# ETH.net
KiCad netlist of a schematic drawn in Altium Designer
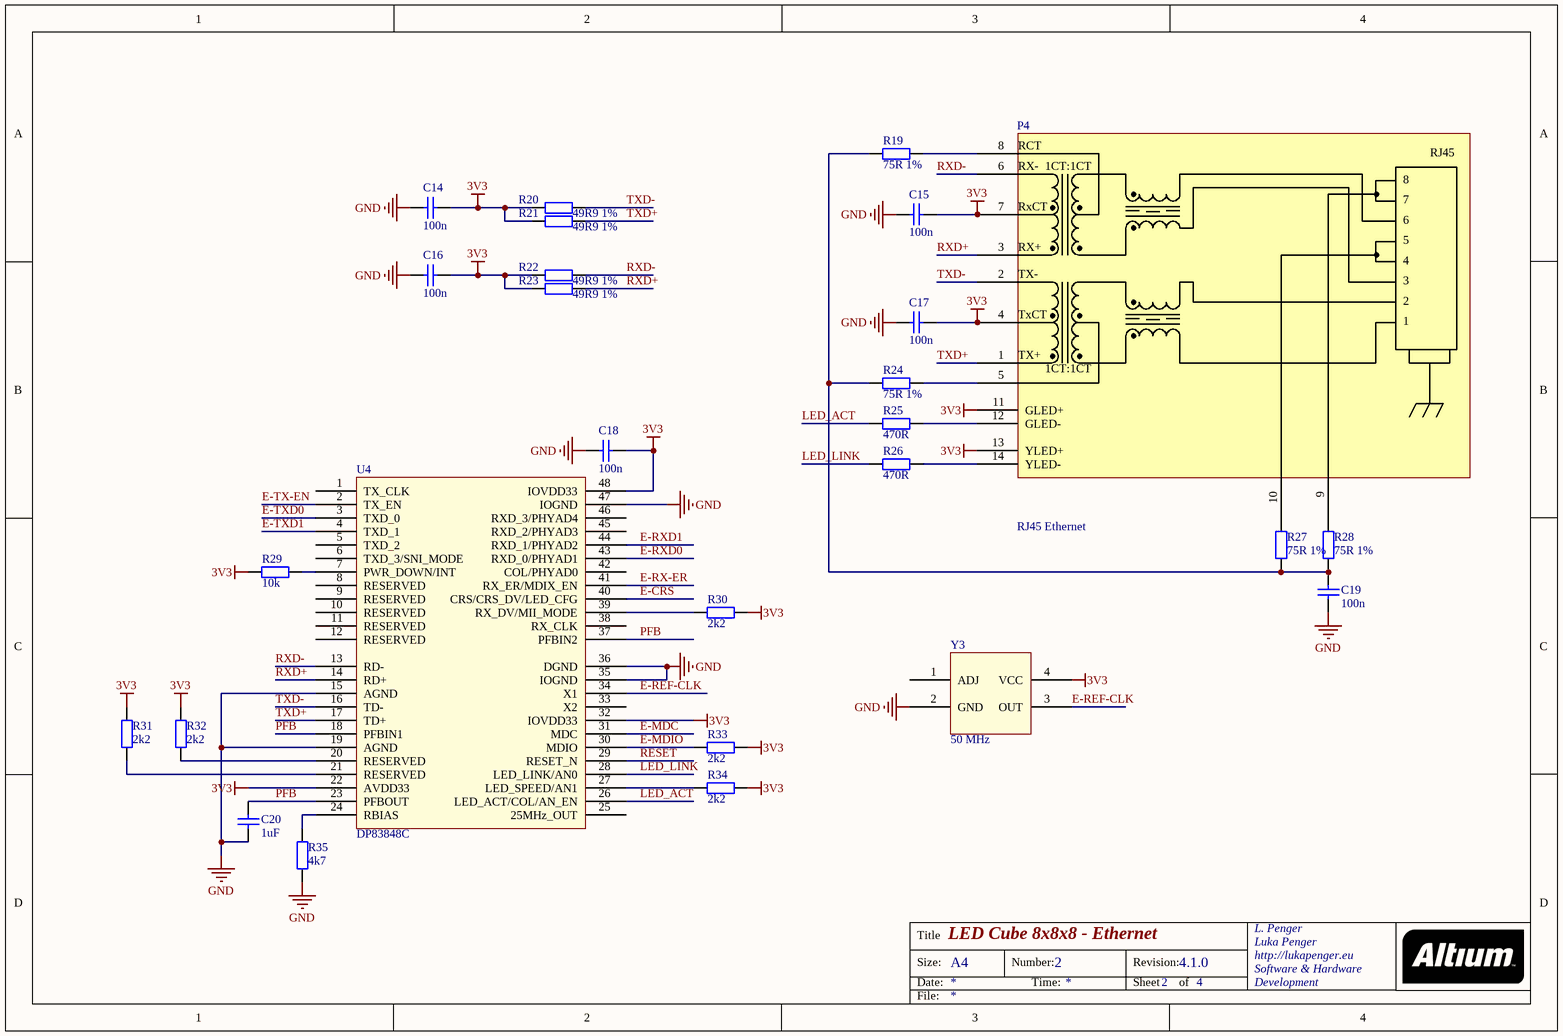
[diagram p0: ETH.SchDoc]

(export (version "E")
  (design (tool "Eeschema 10.0.6"))
  (components
    (comp (ref "C14")
      (value "100n")
      (footprint "1608[0603]")
      (description "Capacitor")
      (fields (field (name "PUBLISHER") "Altium Limited"))
      (libsource (lib "Miscellaneous Devices") (part "Cap"))
    )
    (comp (ref "C15")
      (value "100n")
      (footprint "1608[0603]")
      (description "Capacitor")
      (fields (field (name "PUBLISHER") "Altium Limited"))
      (libsource (lib "Miscellaneous Devices") (part "Cap"))
    )
    (comp (ref "C16")
      (value "100n")
      (footprint "1608[0603]")
      (description "Capacitor")
      (fields (field (name "PUBLISHER") "Altium Limited"))
      (libsource (lib "Miscellaneous Devices") (part "Cap"))
    )
    (comp (ref "C17")
      (value "100n")
      (footprint "1608[0603]")
      (description "Capacitor")
      (fields (field (name "PUBLISHER") "Altium Limited"))
      (libsource (lib "Miscellaneous Devices") (part "Cap"))
    )
    (comp (ref "C18")
      (value "100n")
      (footprint "1608[0603]")
      (description "Capacitor")
      (fields (field (name "PUBLISHER") "Altium Limited"))
      (libsource (lib "Miscellaneous Devices") (part "Cap"))
    )
    (comp (ref "C19")
      (value "100n")
      (footprint "1608[0603]")
      (description "Capacitor")
      (fields (field (name "PUBLISHER") "Altium Limited"))
      (libsource (lib "Miscellaneous Devices") (part "Cap"))
    )
    (comp (ref "C20")
      (value "1uF")
      (footprint "6-0805_L")
      (description "Capacitor")
      (fields (field (name "PUBLISHER") "Altium Limited"))
      (libsource (lib "Miscellaneous Devices") (part "Cap"))
    )
    (comp (ref "P4")
      (value "RJ45 Ethernet")
      (footprint "RJ45 Ethernet connector")
      (description "Ethernet Connector")
      (libsource (lib "LP_Lib") (part "RJ45 Ethernet"))
    )
    (comp (ref "R19")
      (value "75R 1%")
      (footprint "1608[0603]")
      (description "Resistor")
      (fields (field (name "PUBLISHER") "Altium Limited"))
      (libsource (lib "") (part "Res2_1"))
    )
    (comp (ref "R20")
      (value "49R9 1%")
      (footprint "1608[0603]")
      (description "Resistor")
      (fields (field (name "PUBLISHER") "Altium Limited"))
      (libsource (lib "") (part "Res2_1"))
    )
    (comp (ref "R21")
      (value "49R9 1%")
      (footprint "1608[0603]")
      (description "Resistor")
      (fields (field (name "PUBLISHER") "Altium Limited"))
      (libsource (lib "") (part "Res2_1"))
    )
    (comp (ref "R22")
      (value "49R9 1%")
      (footprint "1608[0603]")
      (description "Resistor")
      (fields (field (name "PUBLISHER") "Altium Limited"))
      (libsource (lib "") (part "Res2_1"))
    )
    (comp (ref "R23")
      (value "49R9 1%")
      (footprint "1608[0603]")
      (description "Resistor")
      (fields (field (name "PUBLISHER") "Altium Limited"))
      (libsource (lib "") (part "Res2_1"))
    )
    (comp (ref "R24")
      (value "75R 1%")
      (footprint "1608[0603]")
      (description "Resistor")
      (fields (field (name "PUBLISHER") "Altium Limited"))
      (libsource (lib "") (part "Res2_1"))
    )
    (comp (ref "R25")
      (value "470R")
      (footprint "1608[0603]")
      (description "Resistor")
      (fields (field (name "PUBLISHER") "Altium Limited"))
      (libsource (lib "") (part "Res2_1"))
    )
    (comp (ref "R26")
      (value "470R")
      (footprint "1608[0603]")
      (description "Resistor")
      (fields (field (name "PUBLISHER") "Altium Limited"))
      (libsource (lib "") (part "Res2_1"))
    )
    (comp (ref "R27")
      (value "75R 1%")
      (footprint "1608[0603]")
      (description "Resistor")
      (fields (field (name "PUBLISHER") "Altium Limited"))
      (libsource (lib "Miscellaneous Devices") (part "Res2"))
    )
    (comp (ref "R28")
      (value "75R 1%")
      (footprint "1608[0603]")
      (description "Resistor")
      (fields (field (name "PUBLISHER") "Altium Limited"))
      (libsource (lib "Miscellaneous Devices") (part "Res2"))
    )
    (comp (ref "R29")
      (value "10k")
      (footprint "1608[0603]")
      (description "Resistor")
      (fields (field (name "PUBLISHER") "Altium Limited"))
      (libsource (lib "") (part "Res2_1"))
    )
    (comp (ref "R30")
      (value "2k2")
      (footprint "1608[0603]")
      (description "Resistor")
      (fields (field (name "PUBLISHER") "Altium Limited"))
      (libsource (lib "") (part "Res2_1"))
    )
    (comp (ref "R31")
      (value "2k2")
      (footprint "1608[0603]")
      (description "Resistor")
      (fields (field (name "PUBLISHER") "Altium Limited"))
      (libsource (lib "") (part "Res2_2"))
    )
    (comp (ref "R32")
      (value "2k2")
      (footprint "1608[0603]")
      (description "Resistor")
      (fields (field (name "PUBLISHER") "Altium Limited"))
      (libsource (lib "Miscellaneous Devices") (part "Res2"))
    )
    (comp (ref "R33")
      (value "2k2")
      (footprint "1608[0603]")
      (description "Resistor")
      (fields (field (name "PUBLISHER") "Altium Limited"))
      (libsource (lib "") (part "Res2_1"))
    )
    (comp (ref "R34")
      (value "2k2")
      (footprint "1608[0603]")
      (description "Resistor")
      (fields (field (name "PUBLISHER") "Altium Limited"))
      (libsource (lib "") (part "Res2_1"))
    )
    (comp (ref "R35")
      (value "4k7")
      (footprint "1608[0603]")
      (description "Resistor")
      (fields (field (name "PUBLISHER") "Altium Limited"))
      (libsource (lib "") (part "Res2_2"))
    )
    (comp (ref "U4")
      (value "DP83848C")
      (footprint "DP83848C")
      (description "Ethernet PHY")
      (libsource (lib "LP_Lib") (part "DP83848C"))
    )
    (comp (ref "Y3")
      (value "50 MHz")
      (footprint "XTAL ACT9200 5x7mm")
      (libsource (lib "LukaLIBRARY") (part "XTAL ACT9200"))
    )
  )
  (nets
    (net (code "1") (name "/E-CRS") (class "Default")
      (node (ref "U4") (pin "40") (pinfunction "CRS/CRS_DV/LED_CFG_40") (pintype "passive"))
    )
    (net (code "2") (name "/E-MDC") (class "Default")
      (node (ref "U4") (pin "31") (pinfunction "MDC_31") (pintype "passive"))
    )
    (net (code "3") (name "/E-MDIO") (class "Default")
      (node (ref "R33") (pin "2") (pinfunction "2_2") (pintype "passive"))
      (node (ref "U4") (pin "30") (pinfunction "MDIO_30") (pintype "passive"))
    )
    (net (code "4") (name "/E-REF-CLK") (class "Default")
      (node (ref "U4") (pin "34") (pinfunction "X1_34") (pintype "passive"))
      (node (ref "Y3") (pin "3") (pinfunction "OUT_3") (pintype "passive"))
    )
    (net (code "5") (name "/E-RX-ER") (class "Default")
      (node (ref "U4") (pin "41") (pinfunction "RX_ER/MDIX_EN_41") (pintype "passive"))
    )
    (net (code "6") (name "/E-RXD0") (class "Default")
      (node (ref "U4") (pin "43") (pinfunction "RXD_0/PHYAD1_43") (pintype "passive"))
    )
    (net (code "7") (name "/E-RXD1") (class "Default")
      (node (ref "U4") (pin "44") (pinfunction "RXD_1/PHYAD2_44") (pintype "passive"))
    )
    (net (code "8") (name "/E-TX-EN") (class "Default")
      (node (ref "U4") (pin "2") (pinfunction "TX_EN_2") (pintype "passive"))
    )
    (net (code "9") (name "/E-TXD0") (class "Default")
      (node (ref "U4") (pin "3") (pinfunction "TXD_0_3") (pintype "passive"))
    )
    (net (code "10") (name "/E-TXD1") (class "Default")
      (node (ref "U4") (pin "4") (pinfunction "TXD_1_4") (pintype "passive"))
    )
    (net (code "11") (name "/LED_ACT") (class "Default")
      (node (ref "R25") (pin "2") (pinfunction "2_2") (pintype "passive"))
      (node (ref "U4") (pin "26") (pinfunction "LED_ACT/COL/AN_EN_26") (pintype "passive"))
    )
    (net (code "12") (name "/LED_LINK") (class "Default")
      (node (ref "R26") (pin "2") (pinfunction "2_2") (pintype "passive"))
      (node (ref "U4") (pin "28") (pinfunction "LED_LINK/AN0_28") (pintype "passive"))
    )
    (net (code "13") (name "/PFB") (class "Default")
      (node (ref "C20") (pin "1") (pinfunction "1_1") (pintype "passive"))
      (node (ref "U4") (pin "18") (pinfunction "PFBIN1_18") (pintype "passive"))
      (node (ref "U4") (pin "23") (pinfunction "PFBOUT_23") (pintype "passive"))
      (node (ref "U4") (pin "37") (pinfunction "PFBIN2_37") (pintype "passive"))
    )
    (net (code "14") (name "/RESET") (class "Default")
      (node (ref "U4") (pin "29") (pinfunction "RESET_N_29") (pintype "passive"))
    )
    (net (code "15") (name "/RXD+") (class "Default")
      (node (ref "P4") (pin "3") (pintype "passive"))
      (node (ref "R23") (pin "1") (pinfunction "1_1") (pintype "passive"))
      (node (ref "U4") (pin "14") (pinfunction "RD+_14") (pintype "passive"))
    )
    (net (code "16") (name "/RXD-") (class "Default")
      (node (ref "P4") (pin "6") (pintype "passive"))
      (node (ref "R22") (pin "1") (pinfunction "1_1") (pintype "passive"))
      (node (ref "U4") (pin "13") (pinfunction "RD-_13") (pintype "passive"))
    )
    (net (code "17") (name "/TXD+") (class "Default")
      (node (ref "P4") (pin "1") (pintype "passive"))
      (node (ref "R21") (pin "1") (pinfunction "1_1") (pintype "passive"))
      (node (ref "U4") (pin "17") (pinfunction "TD+_17") (pintype "passive"))
    )
    (net (code "18") (name "/TXD-") (class "Default")
      (node (ref "P4") (pin "2") (pintype "passive"))
      (node (ref "R20") (pin "1") (pinfunction "1_1") (pintype "passive"))
      (node (ref "U4") (pin "16") (pinfunction "TD-_16") (pintype "passive"))
    )
    (net (code "19") (name "3V3") (class "Default")
      (node (ref "C14") (pin "2") (pinfunction "2_2") (pintype "passive"))
      (node (ref "C15") (pin "2") (pinfunction "2_2") (pintype "passive"))
      (node (ref "C16") (pin "2") (pinfunction "2_2") (pintype "passive"))
      (node (ref "C17") (pin "2") (pinfunction "2_2") (pintype "passive"))
      (node (ref "C18") (pin "2") (pinfunction "2_2") (pintype "passive"))
      (node (ref "P4") (pin "11") (pinfunction "GLED+_11") (pintype "passive"))
      (node (ref "P4") (pin "13") (pinfunction "YLED+_13") (pintype "passive"))
      (node (ref "P4") (pin "4") (pintype "passive"))
      (node (ref "P4") (pin "7") (pintype "passive"))
      (node (ref "R20") (pin "2") (pinfunction "2_2") (pintype "passive"))
      (node (ref "R21") (pin "2") (pinfunction "2_2") (pintype "passive"))
      (node (ref "R22") (pin "2") (pinfunction "2_2") (pintype "passive"))
      (node (ref "R23") (pin "2") (pinfunction "2_2") (pintype "passive"))
      (node (ref "R29") (pin "2") (pinfunction "2_2") (pintype "passive"))
      (node (ref "R30") (pin "1") (pinfunction "1_1") (pintype "passive"))
      (node (ref "R31") (pin "1") (pinfunction "1_1") (pintype "passive"))
      (node (ref "R32") (pin "2") (pinfunction "2_2") (pintype "passive"))
      (node (ref "R33") (pin "1") (pinfunction "1_1") (pintype "passive"))
      (node (ref "R34") (pin "1") (pinfunction "1_1") (pintype "passive"))
      (node (ref "U4") (pin "22") (pinfunction "AVDD33_22") (pintype "passive"))
      (node (ref "U4") (pin "32") (pinfunction "IOVDD33_32") (pintype "passive"))
      (node (ref "U4") (pin "48") (pinfunction "IOVDD33_48") (pintype "passive"))
      (node (ref "Y3") (pin "4") (pinfunction "VCC_4") (pintype "passive"))
    )
    (net (code "20") (name "GND") (class "Default")
      (node (ref "C14") (pin "1") (pinfunction "1_1") (pintype "passive"))
      (node (ref "C15") (pin "1") (pinfunction "1_1") (pintype "passive"))
      (node (ref "C16") (pin "1") (pinfunction "1_1") (pintype "passive"))
      (node (ref "C17") (pin "1") (pinfunction "1_1") (pintype "passive"))
      (node (ref "C18") (pin "1") (pinfunction "1_1") (pintype "passive"))
      (node (ref "C19") (pin "2") (pinfunction "2_2") (pintype "passive"))
      (node (ref "C20") (pin "2") (pinfunction "2_2") (pintype "passive"))
      (node (ref "R35") (pin "2") (pinfunction "2_2") (pintype "passive"))
      (node (ref "U4") (pin "15") (pinfunction "AGND_15") (pintype "passive"))
      (node (ref "U4") (pin "19") (pinfunction "AGND_19") (pintype "passive"))
      (node (ref "U4") (pin "35") (pinfunction "IOGND_35") (pintype "passive"))
      (node (ref "U4") (pin "36") (pinfunction "DGND_36") (pintype "passive"))
      (node (ref "U4") (pin "47") (pinfunction "IOGND_47") (pintype "passive"))
      (node (ref "Y3") (pin "2") (pinfunction "GND_2") (pintype "passive"))
    )
    (net (code "21") (name "Net-(C19-Pad1)") (class "Default")
      (node (ref "C19") (pin "1") (pinfunction "1_1") (pintype "passive"))
      (node (ref "R19") (pin "2") (pinfunction "2_2") (pintype "passive"))
      (node (ref "R24") (pin "2") (pinfunction "2_2") (pintype "passive"))
      (node (ref "R27") (pin "1") (pinfunction "1_1") (pintype "passive"))
      (node (ref "R28") (pin "1") (pinfunction "1_1") (pintype "passive"))
    )
    (net (code "22") (name "Net-(P4-GLED-)") (class "Default")
      (node (ref "P4") (pin "12") (pinfunction "GLED-_12") (pintype "passive"))
      (node (ref "R25") (pin "1") (pinfunction "1_1") (pintype "passive"))
    )
    (net (code "23") (name "Net-(P4-Pad5)") (class "Default")
      (node (ref "P4") (pin "5") (pintype "passive"))
      (node (ref "R24") (pin "1") (pinfunction "1_1") (pintype "passive"))
    )
    (net (code "24") (name "Net-(P4-Pad8)") (class "Default")
      (node (ref "P4") (pin "8") (pintype "passive"))
      (node (ref "R19") (pin "1") (pinfunction "1_1") (pintype "passive"))
    )
    (net (code "25") (name "Net-(P4-Pad9)") (class "Default")
      (node (ref "P4") (pin "9") (pintype "passive"))
      (node (ref "R28") (pin "2") (pinfunction "2_2") (pintype "passive"))
    )
    (net (code "26") (name "Net-(P4-Pad10)") (class "Default")
      (node (ref "P4") (pin "10") (pintype "passive"))
      (node (ref "R27") (pin "2") (pinfunction "2_2") (pintype "passive"))
    )
    (net (code "27") (name "Net-(P4-YLED-)") (class "Default")
      (node (ref "P4") (pin "14") (pinfunction "YLED-_14") (pintype "passive"))
      (node (ref "R26") (pin "1") (pinfunction "1_1") (pintype "passive"))
    )
    (net (code "28") (name "Net-(R31-Pad2)") (class "Default")
      (node (ref "R31") (pin "2") (pinfunction "2_2") (pintype "passive"))
      (node (ref "U4") (pin "21") (pinfunction "RESERVED_21") (pintype "passive"))
    )
    (net (code "29") (name "Net-(R32-Pad1)") (class "Default")
      (node (ref "R32") (pin "1") (pinfunction "1_1") (pintype "passive"))
      (node (ref "U4") (pin "20") (pinfunction "RESERVED_20") (pintype "passive"))
    )
    (net (code "30") (name "Net-(U4-LED_SPEED{slash}AN1)") (class "Default")
      (node (ref "R34") (pin "2") (pinfunction "2_2") (pintype "passive"))
      (node (ref "U4") (pin "27") (pinfunction "LED_SPEED/AN1_27") (pintype "passive"))
    )
    (net (code "31") (name "Net-(U4-PWR_DOWN{slash}INT)") (class "Default")
      (node (ref "R29") (pin "1") (pinfunction "1_1") (pintype "passive"))
      (node (ref "U4") (pin "7") (pinfunction "PWR_DOWN/INT_7") (pintype "passive"))
    )
    (net (code "32") (name "Net-(U4-RBIAS)") (class "Default")
      (node (ref "R35") (pin "1") (pinfunction "1_1") (pintype "passive"))
      (node (ref "U4") (pin "24") (pinfunction "RBIAS_24") (pintype "passive"))
    )
    (net (code "33") (name "Net-(U4-RX_DV{slash}MII_MODE)") (class "Default")
      (node (ref "R30") (pin "2") (pinfunction "2_2") (pintype "passive"))
      (node (ref "U4") (pin "39") (pinfunction "RX_DV/MII_MODE_39") (pintype "passive"))
    )
    (net (code "34") (name "unconnected-(U4-25MHz_OUT-Pad25)") (class "Default")
      (node (ref "U4") (pin "25") (pinfunction "25MHz_OUT_25") (pintype "passive"))
    )
    (net (code "35") (name "unconnected-(U4-COL{slash}PHYAD0-Pad42)") (class "Default")
      (node (ref "U4") (pin "42") (pinfunction "COL/PHYAD0_42") (pintype "passive"))
    )
    (net (code "36") (name "unconnected-(U4-RESERVED-Pad8)") (class "Default")
      (node (ref "U4") (pin "8") (pinfunction "RESERVED_8") (pintype "passive"))
    )
    (net (code "37") (name "unconnected-(U4-RESERVED-Pad9)") (class "Default")
      (node (ref "U4") (pin "9") (pinfunction "RESERVED_9") (pintype "passive"))
    )
    (net (code "38") (name "unconnected-(U4-RESERVED-Pad10)") (class "Default")
      (node (ref "U4") (pin "10") (pinfunction "RESERVED_10") (pintype "passive"))
    )
    (net (code "39") (name "unconnected-(U4-RESERVED-Pad11)") (class "Default")
      (node (ref "U4") (pin "11") (pinfunction "RESERVED_11") (pintype "passive"))
    )
    (net (code "40") (name "unconnected-(U4-RESERVED-Pad12)") (class "Default")
      (node (ref "U4") (pin "12") (pinfunction "RESERVED_12") (pintype "passive"))
    )
    (net (code "41") (name "unconnected-(U4-RXD_2{slash}PHYAD3-Pad45)") (class "Default")
      (node (ref "U4") (pin "45") (pinfunction "RXD_2/PHYAD3_45") (pintype "passive"))
    )
    (net (code "42") (name "unconnected-(U4-RXD_3{slash}PHYAD4-Pad46)") (class "Default")
      (node (ref "U4") (pin "46") (pinfunction "RXD_3/PHYAD4_46") (pintype "passive"))
    )
    (net (code "43") (name "unconnected-(U4-RX_CLK-Pad38)") (class "Default")
      (node (ref "U4") (pin "38") (pinfunction "RX_CLK_38") (pintype "passive"))
    )
    (net (code "44") (name "unconnected-(U4-TXD_2-Pad5)") (class "Default")
      (node (ref "U4") (pin "5") (pinfunction "TXD_2_5") (pintype "passive"))
    )
    (net (code "45") (name "unconnected-(U4-TXD_3{slash}SNI_MODE-Pad6)") (class "Default")
      (node (ref "U4") (pin "6") (pinfunction "TXD_3/SNI_MODE_6") (pintype "passive"))
    )
    (net (code "46") (name "unconnected-(U4-TX_CLK-Pad1)") (class "Default")
      (node (ref "U4") (pin "1") (pinfunction "TX_CLK_1") (pintype "passive"))
    )
    (net (code "47") (name "unconnected-(U4-X2-Pad33)") (class "Default")
      (node (ref "U4") (pin "33") (pinfunction "X2_33") (pintype "passive"))
    )
    (net (code "48") (name "unconnected-(Y3-ADJ-Pad1)") (class "Default")
      (node (ref "Y3") (pin "1") (pinfunction "ADJ_1") (pintype "passive"))
    )
  )
)
